# Power_Supply.net
KiCad netlist of a schematic drawn in Altium Designer
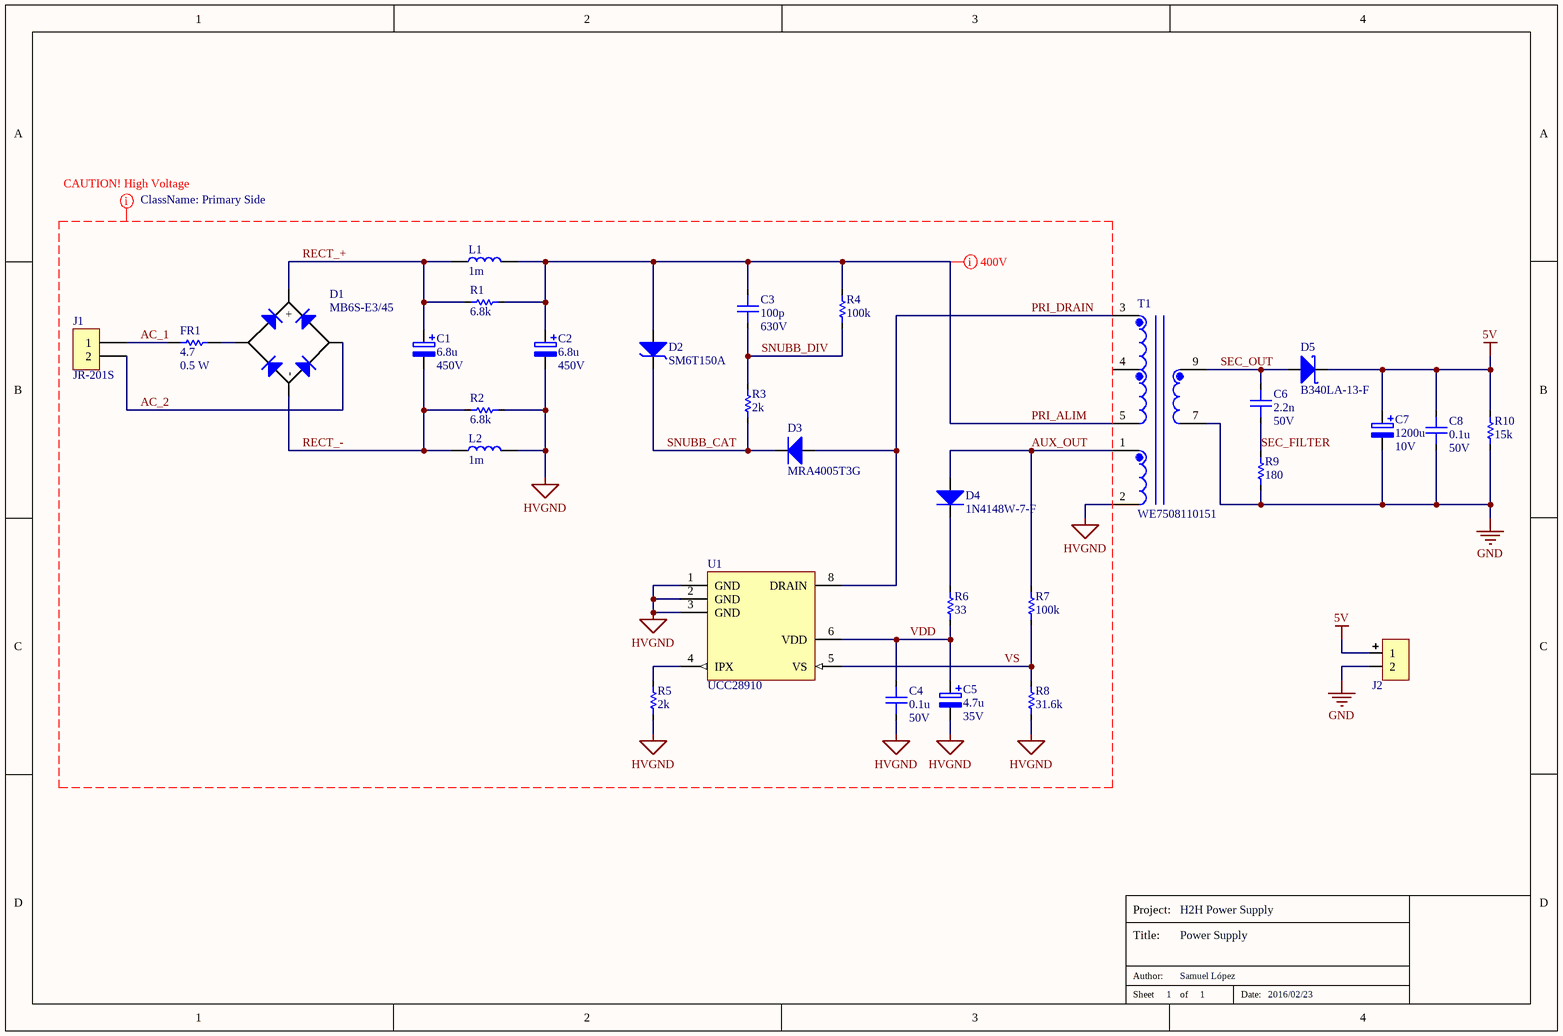
[diagram p0: Power Supply.SchDoc]

(export (version "E")
  (design (tool "Eeschema 10.0.6"))
  (components
    (comp (ref "C1")
      (value "6.8u")
      (footprint "450BXC6R8MEFC10X16")
      (description "Capacitor - Electrolytic Capacitor, 6.8 uF, 450 V, 20%, 10 mm")
      (fields (field (name "RATED VOLTAGE") "450V"))
      (libsource (lib "Supply") (part "450BXC6R8MEFC10X16"))
    )
    (comp (ref "C2")
      (value "6.8u")
      (footprint "450BXC6R8MEFC10X16")
      (description "Capacitor - Electrolytic Capacitor, 6.8 uF, 450 V, 20%, 10 mm")
      (fields (field (name "RATED VOLTAGE") "450V"))
      (libsource (lib "Supply") (part "450BXC6R8MEFC10X16"))
    )
    (comp (ref "C3")
      (value "100p")
      (footprint "C1206")
      (description "Capacitor")
      (fields (field (name "RATED VOLTAGE") "630V"))
      (libsource (lib "Misc") (part "Capacitor"))
    )
    (comp (ref "C4")
      (value "0.1u")
      (footprint "C1206")
      (description "Capacitor")
      (fields (field (name "RATED VOLTAGE") "50V"))
      (libsource (lib "Misc") (part "Capacitor"))
    )
    (comp (ref "C5")
      (value "4.7u")
      (footprint "EXV475M035A9BAA")
      (description "Capacitor - Electrolytic Capacitor, SMD, 4.7 uF, 35 V, 4 mm")
      (fields (field (name "RATED VOLTAGE") "35V"))
      (libsource (lib "Supply") (part "EXV475M035A9BAA"))
    )
    (comp (ref "C6")
      (value "2.2n")
      (footprint "C1206")
      (description "Capacitor")
      (fields (field (name "RATED VOLTAGE") "50V"))
      (libsource (lib "Misc") (part "Capacitor"))
    )
    (comp (ref "C7")
      (value "1200u")
      (footprint "EEUFM1A122")
      (description "Capacitor - Electrolytic Capacitor, 1200 uF, 10 V, 20%, 10 mm")
      (fields (field (name "RATED VOLTAGE") "10V"))
      (libsource (lib "Supply") (part "EEUFM1A122"))
    )
    (comp (ref "C8")
      (value "0.1u")
      (footprint "C1206")
      (description "Capacitor")
      (fields (field (name "RATED VOLTAGE") "50V"))
      (libsource (lib "Misc") (part "Capacitor"))
    )
    (comp (ref "D1")
      (value "MB6S-E3/45")
      (footprint "MB6S-E3/45")
      (description "Diode - Bridge Rectifier, 600 V, 0.5 A")
      (libsource (lib "Supply") (part "MB6S-E3/45"))
    )
    (comp (ref "D2")
      (value "SM6T150A")
      (footprint "SM6T150A")
      (description "TVS - Unidirectional, 150V, 600W")
      (libsource (lib "Supply") (part "SM6T150A"))
    )
    (comp (ref "D3")
      (value "MRA4005T3G")
      (footprint "MRA4005T3G")
      (description "Diode - Standard, 1.1V, 1A, 600V")
      (libsource (lib "Supply") (part "MRA4005T3G"))
    )
    (comp (ref "D4")
      (value "1N4148W-7-F")
      (footprint "1N4148W-7-F")
      (description "Diode - Standard, Switch, 1.25V, 300mA, 100V")
      (libsource (lib "Supply") (part "1N4148W-7-F"))
    )
    (comp (ref "D5")
      (value "B340LA-13-F")
      (footprint "B340LA-13-F")
      (description "Diode - Schottky, 450mV, 3A, 40V")
      (libsource (lib "Supply") (part "B340LA-13-F"))
    )
    (comp (ref "FR1")
      (value "4.7")
      (footprint "NFR25H0004708JA500")
      (description "Resistor - Fusible, Non-flammable Resistor")
      (fields (field (name "POWER") "0.5 W"))
      (libsource (lib "Supply") (part "NFR25H0004708JA500"))
    )
    (comp (ref "J1")
      (value "JR-201S")
      (footprint "JR-201S")
      (description "Conn - 250 V AC, Inlet, IEC, Plug")
      (libsource (lib "Conn") (part "JR-201S"))
    )
    (comp (ref "J2")
      (value "JST PH 2 Pin")
      (footprint "S2B-PH-K-S")
      (description "Conn - Battery, Male, 2 Pin, PCB, Right Angle")
      (libsource (lib "Conn") (part "S2B-PH-K-S"))
    )
    (comp (ref "L1")
      (value "1m")
      (footprint "DR0810-105L")
      (description "Inductor - Power, 1 mH, 0.5 A Sat. Current, 10%")
      (libsource (lib "Supply") (part "DR0810-105L"))
    )
    (comp (ref "L2")
      (value "1m")
      (footprint "DR0810-105L")
      (description "Inductor - Power, 1 mH, 0.5 A Sat. Current, 10%")
      (libsource (lib "Supply") (part "DR0810-105L"))
    )
    (comp (ref "R1")
      (value "6.8k")
      (footprint "R1206")
      (description "Resistor")
      (libsource (lib "Misc") (part "Resistor"))
    )
    (comp (ref "R2")
      (value "6.8k")
      (footprint "R1206")
      (description "Resistor")
      (libsource (lib "Misc") (part "Resistor"))
    )
    (comp (ref "R3")
      (value "2k")
      (footprint "R1206")
      (description "Resistor")
      (libsource (lib "Misc") (part "Resistor"))
    )
    (comp (ref "R4")
      (value "100k")
      (footprint "R1206")
      (description "Resistor")
      (libsource (lib "Misc") (part "Resistor"))
    )
    (comp (ref "R5")
      (value "2k")
      (footprint "R1206")
      (description "Resistor")
      (libsource (lib "Misc") (part "Resistor"))
    )
    (comp (ref "R6")
      (value "33")
      (footprint "R1206")
      (description "Resistor")
      (libsource (lib "Misc") (part "Resistor"))
    )
    (comp (ref "R7")
      (value "100k")
      (footprint "R1206")
      (description "Resistor")
      (libsource (lib "Misc") (part "Resistor"))
    )
    (comp (ref "R8")
      (value "31.6k")
      (footprint "R1206")
      (description "Resistor")
      (libsource (lib "Misc") (part "Resistor"))
    )
    (comp (ref "R9")
      (value "180")
      (footprint "R1206")
      (description "Resistor")
      (libsource (lib "Misc") (part "Resistor"))
    )
    (comp (ref "R10")
      (value "15k")
      (footprint "R1206")
      (description "Resistor")
      (libsource (lib "Misc") (part "Resistor"))
    )
    (comp (ref "T1")
      (value "WE7508110151")
      (footprint "WE7508110151")
      (description "Transformer - Flyback/Offline Transformer")
      (libsource (lib "Supply") (part "WE7508110151"))
    )
    (comp (ref "U1") (value "UCC28910") (footprint "UCC28910") (libsource (lib "Supply") (part "UCC28910")))
  )
  (nets
    (net (code "1") (name "/AC_1") (class "Default")
      (node (ref "FR1") (pin "1") (pinfunction "1_1") (pintype "passive"))
      (node (ref "J1") (pin "1") (pinfunction "1_1") (pintype "passive"))
    )
    (net (code "2") (name "/AC_2") (class "Default")
      (node (ref "D1") (pin "2") (pinfunction "AC_2") (pintype "passive"))
      (node (ref "J1") (pin "2") (pinfunction "2_2") (pintype "passive"))
    )
    (net (code "3") (name "/AUX_OUT") (class "Default")
      (node (ref "D4") (pin "1") (pinfunction "A_1") (pintype "passive"))
      (node (ref "R7") (pin "1") (pinfunction "1_1") (pintype "passive"))
      (node (ref "T1") (pin "1") (pinfunction "Aux1_1") (pintype "passive"))
    )
    (net (code "4") (name "/PRI_ALIM") (class "Default")
      (node (ref "C2") (pin "1") (pinfunction "1_1") (pintype "passive"))
      (node (ref "C3") (pin "1") (pinfunction "1_1") (pintype "passive"))
      (node (ref "D2") (pin "1") (pinfunction "A_1") (pintype "passive"))
      (node (ref "L1") (pin "2") (pinfunction "2_2") (pintype "passive"))
      (node (ref "R1") (pin "2") (pinfunction "2_2") (pintype "passive"))
      (node (ref "R4") (pin "1") (pinfunction "1_1") (pintype "passive"))
      (node (ref "T1") (pin "5") (pinfunction "Pri3_5") (pintype "passive"))
    )
    (net (code "5") (name "/PRI_DRAIN") (class "Default")
      (node (ref "D3") (pin "1") (pinfunction "A_1") (pintype "passive"))
      (node (ref "T1") (pin "3") (pinfunction "Pri1_3") (pintype "passive"))
      (node (ref "U1") (pin "8") (pinfunction "DRAIN_8") (pintype "passive"))
    )
    (net (code "6") (name "/RECT_+") (class "Default")
      (node (ref "C1") (pin "1") (pinfunction "1_1") (pintype "passive"))
      (node (ref "D1") (pin "3") (pinfunction "+_3") (pintype "passive"))
      (node (ref "L1") (pin "1") (pinfunction "1_1") (pintype "passive"))
      (node (ref "R1") (pin "1") (pinfunction "1_1") (pintype "passive"))
    )
    (net (code "7") (name "/RECT_-") (class "Default")
      (node (ref "C1") (pin "2") (pinfunction "2_2") (pintype "passive"))
      (node (ref "D1") (pin "4") (pinfunction "-_4") (pintype "passive"))
      (node (ref "L2") (pin "1") (pinfunction "1_1") (pintype "passive"))
      (node (ref "R2") (pin "1") (pinfunction "1_1") (pintype "passive"))
    )
    (net (code "8") (name "/SEC_FILTER") (class "Default")
      (node (ref "C6") (pin "2") (pinfunction "2_2") (pintype "passive"))
      (node (ref "R9") (pin "1") (pinfunction "1_1") (pintype "passive"))
    )
    (net (code "9") (name "/SEC_OUT") (class "Default")
      (node (ref "C6") (pin "1") (pinfunction "1_1") (pintype "passive"))
      (node (ref "D5") (pin "1") (pinfunction "A_1") (pintype "passive"))
      (node (ref "T1") (pin "9") (pinfunction "Sec1_9") (pintype "passive"))
    )
    (net (code "10") (name "/SNUBB_CAT") (class "Default")
      (node (ref "D2") (pin "2") (pinfunction "K_2") (pintype "passive"))
      (node (ref "D3") (pin "2") (pinfunction "K_2") (pintype "passive"))
      (node (ref "R3") (pin "2") (pinfunction "2_2") (pintype "passive"))
    )
    (net (code "11") (name "/SNUBB_DIV") (class "Default")
      (node (ref "C3") (pin "2") (pinfunction "2_2") (pintype "passive"))
      (node (ref "R3") (pin "1") (pinfunction "1_1") (pintype "passive"))
      (node (ref "R4") (pin "2") (pinfunction "2_2") (pintype "passive"))
    )
    (net (code "12") (name "/VDD") (class "Default")
      (node (ref "C4") (pin "1") (pinfunction "1_1") (pintype "passive"))
      (node (ref "C5") (pin "1") (pinfunction "1_1") (pintype "passive"))
      (node (ref "R6") (pin "2") (pinfunction "2_2") (pintype "passive"))
      (node (ref "U1") (pin "6") (pinfunction "VDD_6") (pintype "power_in"))
    )
    (net (code "13") (name "/VS") (class "Default")
      (node (ref "R7") (pin "2") (pinfunction "2_2") (pintype "passive"))
      (node (ref "R8") (pin "1") (pinfunction "1_1") (pintype "passive"))
      (node (ref "U1") (pin "5") (pinfunction "VS_5") (pintype "input"))
    )
    (net (code "14") (name "5V") (class "Default")
      (node (ref "C7") (pin "1") (pinfunction "1_1") (pintype "passive"))
      (node (ref "C8") (pin "1") (pinfunction "1_1") (pintype "passive"))
      (node (ref "D5") (pin "2") (pinfunction "K_2") (pintype "passive"))
      (node (ref "J2") (pin "1") (pinfunction "1_1") (pintype "passive"))
      (node (ref "R10") (pin "1") (pinfunction "1_1") (pintype "passive"))
    )
    (net (code "15") (name "GND") (class "Default")
      (node (ref "C7") (pin "2") (pinfunction "2_2") (pintype "passive"))
      (node (ref "C8") (pin "2") (pinfunction "2_2") (pintype "passive"))
      (node (ref "J2") (pin "2") (pinfunction "2_2") (pintype "passive"))
      (node (ref "R10") (pin "2") (pinfunction "2_2") (pintype "passive"))
      (node (ref "R9") (pin "2") (pinfunction "2_2") (pintype "passive"))
      (node (ref "T1") (pin "7") (pinfunction "Sec2_7") (pintype "passive"))
    )
    (net (code "16") (name "HVGND") (class "Default")
      (node (ref "C2") (pin "2") (pinfunction "2_2") (pintype "passive"))
      (node (ref "C4") (pin "2") (pinfunction "2_2") (pintype "passive"))
      (node (ref "C5") (pin "2") (pinfunction "2_2") (pintype "passive"))
      (node (ref "L2") (pin "2") (pinfunction "2_2") (pintype "passive"))
      (node (ref "R2") (pin "2") (pinfunction "2_2") (pintype "passive"))
      (node (ref "R5") (pin "2") (pinfunction "2_2") (pintype "passive"))
      (node (ref "R8") (pin "2") (pinfunction "2_2") (pintype "passive"))
      (node (ref "T1") (pin "2") (pinfunction "Aux2_2") (pintype "passive"))
      (node (ref "U1") (pin "1") (pinfunction "GND_1") (pintype "power_in"))
      (node (ref "U1") (pin "2") (pinfunction "GND_2") (pintype "power_in"))
      (node (ref "U1") (pin "3") (pinfunction "GND_3") (pintype "power_in"))
    )
    (net (code "17") (name "Net-(D1-AC-Pad1)") (class "Default")
      (node (ref "D1") (pin "1") (pinfunction "AC_1") (pintype "passive"))
      (node (ref "FR1") (pin "2") (pinfunction "2_2") (pintype "passive"))
    )
    (net (code "18") (name "Net-(D4-K)") (class "Default")
      (node (ref "D4") (pin "2") (pinfunction "K_2") (pintype "passive"))
      (node (ref "R6") (pin "1") (pinfunction "1_1") (pintype "passive"))
    )
    (net (code "19") (name "Net-(U1-IPX)") (class "Default")
      (node (ref "R5") (pin "1") (pinfunction "1_1") (pintype "passive"))
      (node (ref "U1") (pin "4") (pinfunction "IPX_4") (pintype "output"))
    )
    (net (code "20") (name "unconnected-(T1-Pri2-Pad4)") (class "Default")
      (node (ref "T1") (pin "4") (pinfunction "Pri2_4") (pintype "passive"))
    )
  )
)
